# v2_0.net
KiCad netlist of a schematic drawn in EAGLE
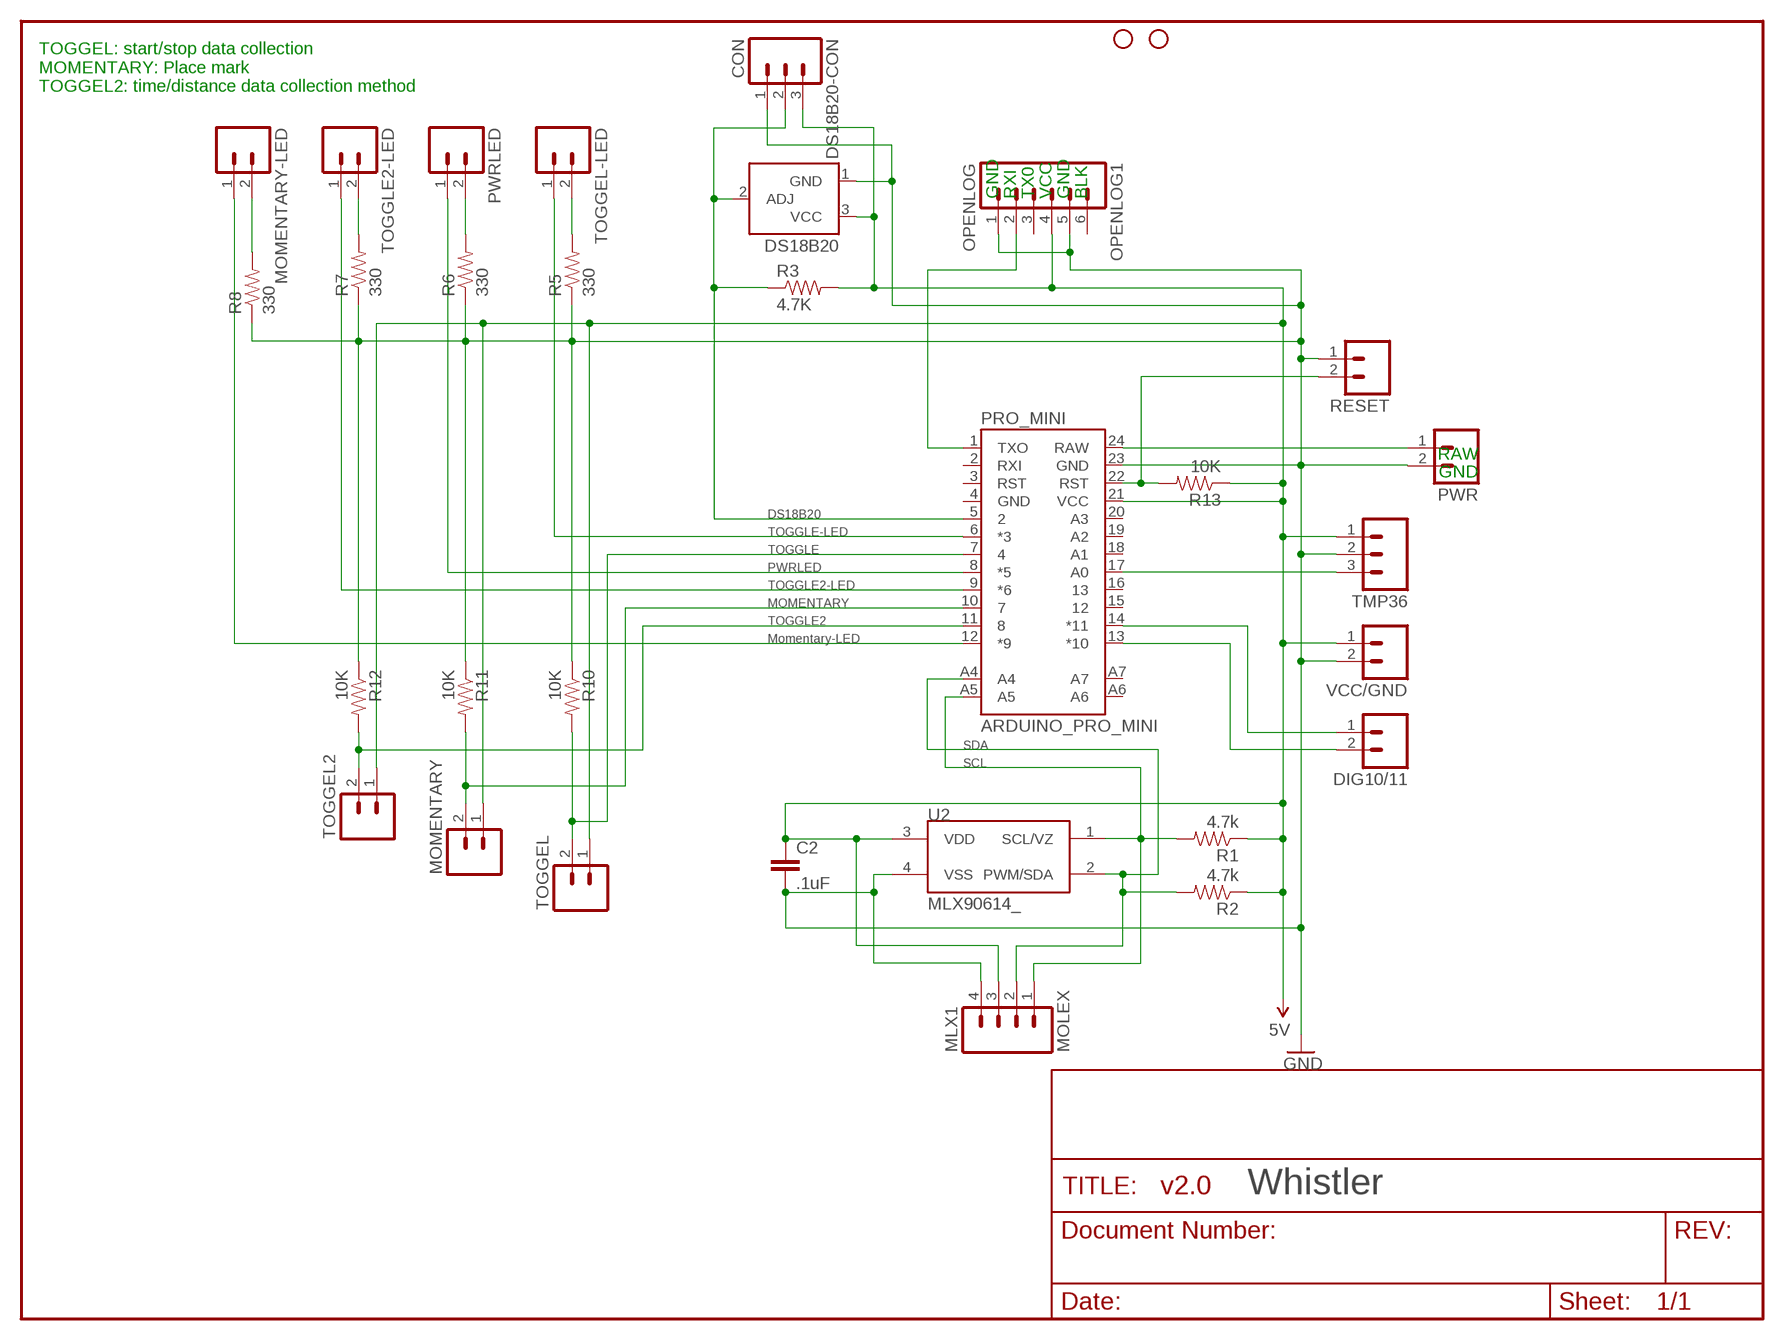
[diagram p0: schematic, sheet 1]

(export (version "E")
  (design (tool "Eeschema 10.0.6"))
  (components
    (comp (ref "C2")
      (value ".1uF")
      (footprint "eagle-import:CAP-PTH-SMALL-KIT")
      (libsource (lib "eagle-import") (part "0.1UF-50V-20%(PTH)KIT-EZ"))
    )
    (comp (ref "DIG10/11")
      (value "M023.5MM_LOCK")
      (footprint "eagle-import:SCREWTERMINAL-3.5MM-2_LOCK")
      (libsource (lib "eagle-import") (part "M023.5MM_LOCK"))
    )
    (comp (ref "DS18B20")
      (value "TEMPERATURE-SENSOR")
      (footprint "eagle-import:TO-92")
      (libsource (lib "eagle-import") (part "TEMPERATURE-SENSOR"))
    )
    (comp (ref "DS18B20-CON")
      (value "CON")
      (footprint "eagle-import:SCREWTERMINAL-3.5MM-3_LOCK.007S")
      (libsource (lib "eagle-import") (part "M03SCREW_LOCK"))
    )
    (comp (ref "JP6")
      (value "STAND-OFFTIGHT")
      (footprint "eagle-import:STAND-OFF-TIGHT")
      (libsource (lib "eagle-import") (part "STAND-OFFTIGHT"))
    )
    (comp (ref "JP7")
      (value "STAND-OFFTIGHT")
      (footprint "eagle-import:STAND-OFF-TIGHT")
      (libsource (lib "eagle-import") (part "STAND-OFFTIGHT"))
    )
    (comp (ref "MLX1")
      (value "MOLEX")
      (footprint "eagle-import:1X04-1MM-RA")
      (libsource (lib "eagle-import") (part "M04SMD2"))
    )
    (comp (ref "MOMENTARY")
      (value "M023.5MM_LOCK")
      (footprint "eagle-import:SCREWTERMINAL-3.5MM-2_LOCK")
      (libsource (lib "eagle-import") (part "M023.5MM_LOCK"))
    )
    (comp (ref "MOMENTARY-LED")
      (value "M023.5MM_LOCK")
      (footprint "eagle-import:SCREWTERMINAL-3.5MM-2_LOCK")
      (libsource (lib "eagle-import") (part "M023.5MM_LOCK"))
    )
    (comp (ref "OPENLOG1")
      (value "OPENLOG")
      (footprint "eagle-import:1X06_LOCK")
      (libsource (lib "eagle-import") (part "M06LOCK"))
    )
    (comp (ref "PRO_MINI")
      (value "ARDUINO_PRO_MINI")
      (footprint "eagle-import:ARDUINO_PRO_MINI")
      (libsource (lib "eagle-import") (part "ARDUINO_PRO_MINI"))
    )
    (comp (ref "PWR")
      (value "M023.5MM_LOCK")
      (footprint "eagle-import:SCREWTERMINAL-3.5MM-2_LOCK")
      (libsource (lib "eagle-import") (part "M023.5MM_LOCK"))
    )
    (comp (ref "PWRLED")
      (value "M023.5MM_LOCK")
      (footprint "eagle-import:SCREWTERMINAL-3.5MM-2_LOCK")
      (libsource (lib "eagle-import") (part "M023.5MM_LOCK"))
    )
    (comp (ref "R1")
      (value "4.7k")
      (footprint "eagle-import:AXIAL-0.4")
      (libsource (lib "eagle-import") (part "RESISTORPTH-1/4W"))
    )
    (comp (ref "R2")
      (value "4.7k")
      (footprint "eagle-import:AXIAL-0.4")
      (libsource (lib "eagle-import") (part "RESISTORPTH-1/4W"))
    )
    (comp (ref "R3")
      (value "4.7K")
      (footprint "eagle-import:AXIAL-0.4")
      (libsource (lib "eagle-import") (part "RESISTORPTH-1/4W"))
    )
    (comp (ref "R5")
      (value "330")
      (footprint "eagle-import:0603-RES")
      (libsource (lib "eagle-import") (part "330OHM1/10W1%(0603)"))
    )
    (comp (ref "R6")
      (value "330")
      (footprint "eagle-import:0603-RES")
      (libsource (lib "eagle-import") (part "330OHM1/10W1%(0603)"))
    )
    (comp (ref "R7")
      (value "330")
      (footprint "eagle-import:0603-RES")
      (libsource (lib "eagle-import") (part "330OHM1/10W1%(0603)"))
    )
    (comp (ref "R8")
      (value "330")
      (footprint "eagle-import:0603-RES")
      (libsource (lib "eagle-import") (part "330OHM1/10W1%(0603)"))
    )
    (comp (ref "R10")
      (value "10K")
      (footprint "eagle-import:0603-RES")
      (libsource (lib "eagle-import") (part "10KOHM1/10W1%(0603)0603"))
    )
    (comp (ref "R11")
      (value "10K")
      (footprint "eagle-import:0603-RES")
      (libsource (lib "eagle-import") (part "10KOHM1/10W1%(0603)0603"))
    )
    (comp (ref "R12")
      (value "10K")
      (footprint "eagle-import:0603-RES")
      (libsource (lib "eagle-import") (part "10KOHM1/10W1%(0603)0603"))
    )
    (comp (ref "R13")
      (value "10K")
      (footprint "eagle-import:0603-RES")
      (libsource (lib "eagle-import") (part "10KOHM1/10W1%(0603)0603"))
    )
    (comp (ref "RESET")
      (value "M023.5MM_LOCK")
      (footprint "eagle-import:SCREWTERMINAL-3.5MM-2_LOCK")
      (libsource (lib "eagle-import") (part "M023.5MM_LOCK"))
    )
    (comp (ref "TMP36")
      (value "M03SCREW_LOCK")
      (footprint "eagle-import:SCREWTERMINAL-3.5MM-3_LOCK.007S")
      (libsource (lib "eagle-import") (part "M03SCREW_LOCK"))
    )
    (comp (ref "TOGGEL")
      (value "M023.5MM_LOCK")
      (footprint "eagle-import:SCREWTERMINAL-3.5MM-2_LOCK")
      (libsource (lib "eagle-import") (part "M023.5MM_LOCK"))
    )
    (comp (ref "TOGGEL-LED")
      (value "M023.5MM_LOCK")
      (footprint "eagle-import:SCREWTERMINAL-3.5MM-2_LOCK")
      (libsource (lib "eagle-import") (part "M023.5MM_LOCK"))
    )
    (comp (ref "TOGGEL2")
      (value "M023.5MM_LOCK")
      (footprint "eagle-import:SCREWTERMINAL-3.5MM-2_LOCK")
      (libsource (lib "eagle-import") (part "M023.5MM_LOCK"))
    )
    (comp (ref "TOGGLE2-LED")
      (value "M023.5MM_LOCK")
      (footprint "eagle-import:SCREWTERMINAL-3.5MM-2_LOCK")
      (libsource (lib "eagle-import") (part "M023.5MM_LOCK"))
    )
    (comp (ref "U2")
      (value "MLX90614_")
      (footprint "eagle-import:TO-39")
      (libsource (lib "eagle-import") (part "MLX90614_"))
    )
    (comp (ref "VCC/GND")
      (value "M023.5MM_LOCK")
      (footprint "eagle-import:SCREWTERMINAL-3.5MM-2_LOCK")
      (libsource (lib "eagle-import") (part "M023.5MM_LOCK"))
    )
  )
  (nets
    (net (code "1") (name "5V") (class "Default")
      (node (ref "C2") (pin "1") (pinfunction "1_1") (pintype "passive"))
      (node (ref "DS18B20") (pin "3") (pinfunction "VCC_3") (pintype "bidirectional"))
      (node (ref "DS18B20-CON") (pin "3") (pinfunction "3_3") (pintype "passive"))
      (node (ref "MLX1") (pin "3") (pinfunction "3_3") (pintype "passive"))
      (node (ref "MOMENTARY") (pin "1") (pinfunction "1_1") (pintype "passive"))
      (node (ref "OPENLOG1") (pin "4") (pinfunction "4_4") (pintype "passive"))
      (node (ref "PRO_MINI") (pin "21") (pinfunction "VCC_21") (pintype "bidirectional"))
      (node (ref "R1") (pin "P$1") (pinfunction "1_P$1") (pintype "passive"))
      (node (ref "R13") (pin "1") (pinfunction "1_1") (pintype "passive"))
      (node (ref "R2") (pin "P$1") (pinfunction "1_P$1") (pintype "passive"))
      (node (ref "R3") (pin "P$2") (pinfunction "2_P$2") (pintype "passive"))
      (node (ref "TMP36") (pin "1") (pinfunction "1_1") (pintype "passive"))
      (node (ref "TOGGEL") (pin "1") (pinfunction "1_1") (pintype "passive"))
      (node (ref "TOGGEL2") (pin "1") (pinfunction "1_1") (pintype "passive"))
      (node (ref "U2") (pin "3") (pinfunction "VDD_3") (pintype "bidirectional"))
      (node (ref "VCC/GND") (pin "1") (pinfunction "1_1") (pintype "passive"))
    )
    (net (code "2") (name "GND") (class "Default")
      (node (ref "C2") (pin "2") (pinfunction "2_2") (pintype "passive"))
      (node (ref "DS18B20") (pin "1") (pinfunction "GND_1") (pintype "bidirectional"))
      (node (ref "DS18B20-CON") (pin "1") (pinfunction "1_1") (pintype "passive"))
      (node (ref "MLX1") (pin "4") (pinfunction "4_4") (pintype "passive"))
      (node (ref "OPENLOG1") (pin "1") (pinfunction "1_1") (pintype "passive"))
      (node (ref "OPENLOG1") (pin "5") (pinfunction "5_5") (pintype "passive"))
      (node (ref "PRO_MINI") (pin "23") (pinfunction "GND_23") (pintype "bidirectional"))
      (node (ref "PWR") (pin "2") (pinfunction "2_2") (pintype "passive"))
      (node (ref "R10") (pin "1") (pinfunction "1_1") (pintype "passive"))
      (node (ref "R11") (pin "1") (pinfunction "1_1") (pintype "passive"))
      (node (ref "R12") (pin "1") (pinfunction "1_1") (pintype "passive"))
      (node (ref "R5") (pin "1") (pinfunction "1_1") (pintype "passive"))
      (node (ref "R6") (pin "1") (pinfunction "1_1") (pintype "passive"))
      (node (ref "R7") (pin "1") (pinfunction "1_1") (pintype "passive"))
      (node (ref "R8") (pin "1") (pinfunction "1_1") (pintype "passive"))
      (node (ref "RESET") (pin "1") (pinfunction "1_1") (pintype "passive"))
      (node (ref "TMP36") (pin "2") (pinfunction "2_2") (pintype "passive"))
      (node (ref "U2") (pin "4") (pinfunction "VSS_4") (pintype "bidirectional"))
      (node (ref "VCC/GND") (pin "2") (pinfunction "2_2") (pintype "passive"))
    )
    (net (code "3") (name "Net-(DS18B20-ADJ)") (class "Default")
      (node (ref "DS18B20") (pin "2") (pinfunction "ADJ_2") (pintype "bidirectional"))
      (node (ref "DS18B20-CON") (pin "2") (pinfunction "2_2") (pintype "passive"))
      (node (ref "PRO_MINI") (pin "5") (pinfunction "2_5") (pintype "bidirectional"))
      (node (ref "R3") (pin "P$1") (pinfunction "1_P$1") (pintype "passive"))
    )
    (net (code "4") (name "Net-(MOMENTARY-LED-Pad2)") (class "Default")
      (node (ref "MOMENTARY-LED") (pin "2") (pinfunction "2_2") (pintype "passive"))
      (node (ref "R8") (pin "2") (pinfunction "2_2") (pintype "passive"))
    )
    (net (code "5") (name "Net-(PRO_MINI-*3)") (class "Default")
      (node (ref "PRO_MINI") (pin "6") (pinfunction "*3_6") (pintype "bidirectional"))
      (node (ref "TOGGEL-LED") (pin "1") (pinfunction "1_1") (pintype "passive"))
    )
    (net (code "6") (name "Net-(PRO_MINI-*5)") (class "Default")
      (node (ref "PRO_MINI") (pin "8") (pinfunction "*5_8") (pintype "bidirectional"))
      (node (ref "PWRLED") (pin "1") (pinfunction "1_1") (pintype "passive"))
    )
    (net (code "7") (name "Net-(PRO_MINI-*6)") (class "Default")
      (node (ref "PRO_MINI") (pin "9") (pinfunction "*6_9") (pintype "bidirectional"))
      (node (ref "TOGGLE2-LED") (pin "1") (pinfunction "1_1") (pintype "passive"))
    )
    (net (code "8") (name "Net-(PRO_MINI-*9)") (class "Default")
      (node (ref "MOMENTARY-LED") (pin "1") (pinfunction "1_1") (pintype "passive"))
      (node (ref "PRO_MINI") (pin "12") (pinfunction "*9_12") (pintype "bidirectional"))
    )
    (net (code "9") (name "Net-(PRO_MINI-*10)") (class "Default")
      (node (ref "DIG10/11") (pin "2") (pinfunction "2_2") (pintype "passive"))
      (node (ref "PRO_MINI") (pin "13") (pinfunction "*10_13") (pintype "bidirectional"))
    )
    (net (code "10") (name "Net-(PRO_MINI-*11)") (class "Default")
      (node (ref "DIG10/11") (pin "1") (pinfunction "1_1") (pintype "passive"))
      (node (ref "PRO_MINI") (pin "14") (pinfunction "*11_14") (pintype "bidirectional"))
    )
    (net (code "11") (name "Net-(PRO_MINI-4)") (class "Default")
      (node (ref "PRO_MINI") (pin "7") (pinfunction "4_7") (pintype "bidirectional"))
      (node (ref "R10") (pin "2") (pinfunction "2_2") (pintype "passive"))
      (node (ref "TOGGEL") (pin "2") (pinfunction "2_2") (pintype "passive"))
    )
    (net (code "12") (name "Net-(PRO_MINI-7)") (class "Default")
      (node (ref "MOMENTARY") (pin "2") (pinfunction "2_2") (pintype "passive"))
      (node (ref "PRO_MINI") (pin "10") (pinfunction "7_10") (pintype "bidirectional"))
      (node (ref "R11") (pin "2") (pinfunction "2_2") (pintype "passive"))
    )
    (net (code "13") (name "Net-(PRO_MINI-8)") (class "Default")
      (node (ref "PRO_MINI") (pin "11") (pinfunction "8_11") (pintype "bidirectional"))
      (node (ref "R12") (pin "2") (pinfunction "2_2") (pintype "passive"))
      (node (ref "TOGGEL2") (pin "2") (pinfunction "2_2") (pintype "passive"))
    )
    (net (code "14") (name "Net-(PRO_MINI-A0)") (class "Default")
      (node (ref "PRO_MINI") (pin "17") (pinfunction "A0_17") (pintype "bidirectional"))
      (node (ref "TMP36") (pin "3") (pinfunction "3_3") (pintype "passive"))
    )
    (net (code "15") (name "Net-(PRO_MINI-RAW)") (class "Default")
      (node (ref "PRO_MINI") (pin "24") (pinfunction "RAW_24") (pintype "bidirectional"))
      (node (ref "PWR") (pin "1") (pinfunction "1_1") (pintype "passive"))
    )
    (net (code "16") (name "Net-(PRO_MINI-RST-Pad22)") (class "Default")
      (node (ref "PRO_MINI") (pin "22") (pinfunction "RST_22") (pintype "bidirectional"))
      (node (ref "R13") (pin "2") (pinfunction "2_2") (pintype "passive"))
      (node (ref "RESET") (pin "2") (pinfunction "2_2") (pintype "passive"))
    )
    (net (code "17") (name "Net-(PRO_MINI-TXO)") (class "Default")
      (node (ref "OPENLOG1") (pin "2") (pinfunction "2_2") (pintype "passive"))
      (node (ref "PRO_MINI") (pin "1") (pinfunction "TXO_1") (pintype "bidirectional"))
    )
    (net (code "18") (name "Net-(PWRLED-Pad2)") (class "Default")
      (node (ref "PWRLED") (pin "2") (pinfunction "2_2") (pintype "passive"))
      (node (ref "R6") (pin "2") (pinfunction "2_2") (pintype "passive"))
    )
    (net (code "19") (name "Net-(R1-2)") (class "Default")
      (node (ref "MLX1") (pin "1") (pinfunction "1_1") (pintype "passive"))
      (node (ref "PRO_MINI") (pin "A5") (pinfunction "A5_A5") (pintype "bidirectional"))
      (node (ref "R1") (pin "P$2") (pinfunction "2_P$2") (pintype "passive"))
      (node (ref "U2") (pin "1") (pinfunction "SCL/VZ_1") (pintype "bidirectional"))
    )
    (net (code "20") (name "Net-(R2-2)") (class "Default")
      (node (ref "MLX1") (pin "2") (pinfunction "2_2") (pintype "passive"))
      (node (ref "PRO_MINI") (pin "A4") (pinfunction "A4_A4") (pintype "bidirectional"))
      (node (ref "R2") (pin "P$2") (pinfunction "2_P$2") (pintype "passive"))
      (node (ref "U2") (pin "2") (pinfunction "PWM/SDA_2") (pintype "bidirectional"))
    )
    (net (code "21") (name "Net-(R5-Pad2)") (class "Default")
      (node (ref "R5") (pin "2") (pinfunction "2_2") (pintype "passive"))
      (node (ref "TOGGEL-LED") (pin "2") (pinfunction "2_2") (pintype "passive"))
    )
    (net (code "22") (name "Net-(R7-Pad2)") (class "Default")
      (node (ref "R7") (pin "2") (pinfunction "2_2") (pintype "passive"))
      (node (ref "TOGGLE2-LED") (pin "2") (pinfunction "2_2") (pintype "passive"))
    )
    (net (code "23") (name "unconnected-(OPENLOG1-Pad3)") (class "Default")
      (node (ref "OPENLOG1") (pin "3") (pinfunction "3_3") (pintype "passive"))
    )
    (net (code "24") (name "unconnected-(OPENLOG1-Pad6)") (class "Default")
      (node (ref "OPENLOG1") (pin "6") (pinfunction "6_6") (pintype "passive"))
    )
    (net (code "25") (name "unconnected-(PRO_MINI-12-Pad15)") (class "Default")
      (node (ref "PRO_MINI") (pin "15") (pinfunction "12_15") (pintype "bidirectional"))
    )
    (net (code "26") (name "unconnected-(PRO_MINI-13-Pad16)") (class "Default")
      (node (ref "PRO_MINI") (pin "16") (pinfunction "13_16") (pintype "bidirectional"))
    )
    (net (code "27") (name "unconnected-(PRO_MINI-A1-Pad18)") (class "Default")
      (node (ref "PRO_MINI") (pin "18") (pinfunction "A1_18") (pintype "bidirectional"))
    )
    (net (code "28") (name "unconnected-(PRO_MINI-A2-Pad19)") (class "Default")
      (node (ref "PRO_MINI") (pin "19") (pinfunction "A2_19") (pintype "bidirectional"))
    )
    (net (code "29") (name "unconnected-(PRO_MINI-A3-Pad20)") (class "Default")
      (node (ref "PRO_MINI") (pin "20") (pinfunction "A3_20") (pintype "bidirectional"))
    )
    (net (code "30") (name "unconnected-(PRO_MINI-GND-Pad4)") (class "Default")
      (node (ref "PRO_MINI") (pin "4") (pinfunction "GND_4") (pintype "bidirectional"))
    )
    (net (code "31") (name "unconnected-(PRO_MINI-PadA6)") (class "Default")
      (node (ref "PRO_MINI") (pin "A6") (pinfunction "A6_A6") (pintype "bidirectional"))
    )
    (net (code "32") (name "unconnected-(PRO_MINI-PadA7)") (class "Default")
      (node (ref "PRO_MINI") (pin "A7") (pinfunction "A7_A7") (pintype "bidirectional"))
    )
    (net (code "33") (name "unconnected-(PRO_MINI-RST-Pad3)") (class "Default")
      (node (ref "PRO_MINI") (pin "3") (pinfunction "RST_3") (pintype "bidirectional"))
    )
    (net (code "34") (name "unconnected-(PRO_MINI-RXI-Pad2)") (class "Default")
      (node (ref "PRO_MINI") (pin "2") (pinfunction "RXI_2") (pintype "bidirectional"))
    )
  )
)
